# LNA_BFU550.net
KiCad netlist of a schematic drawn in Altium Designer
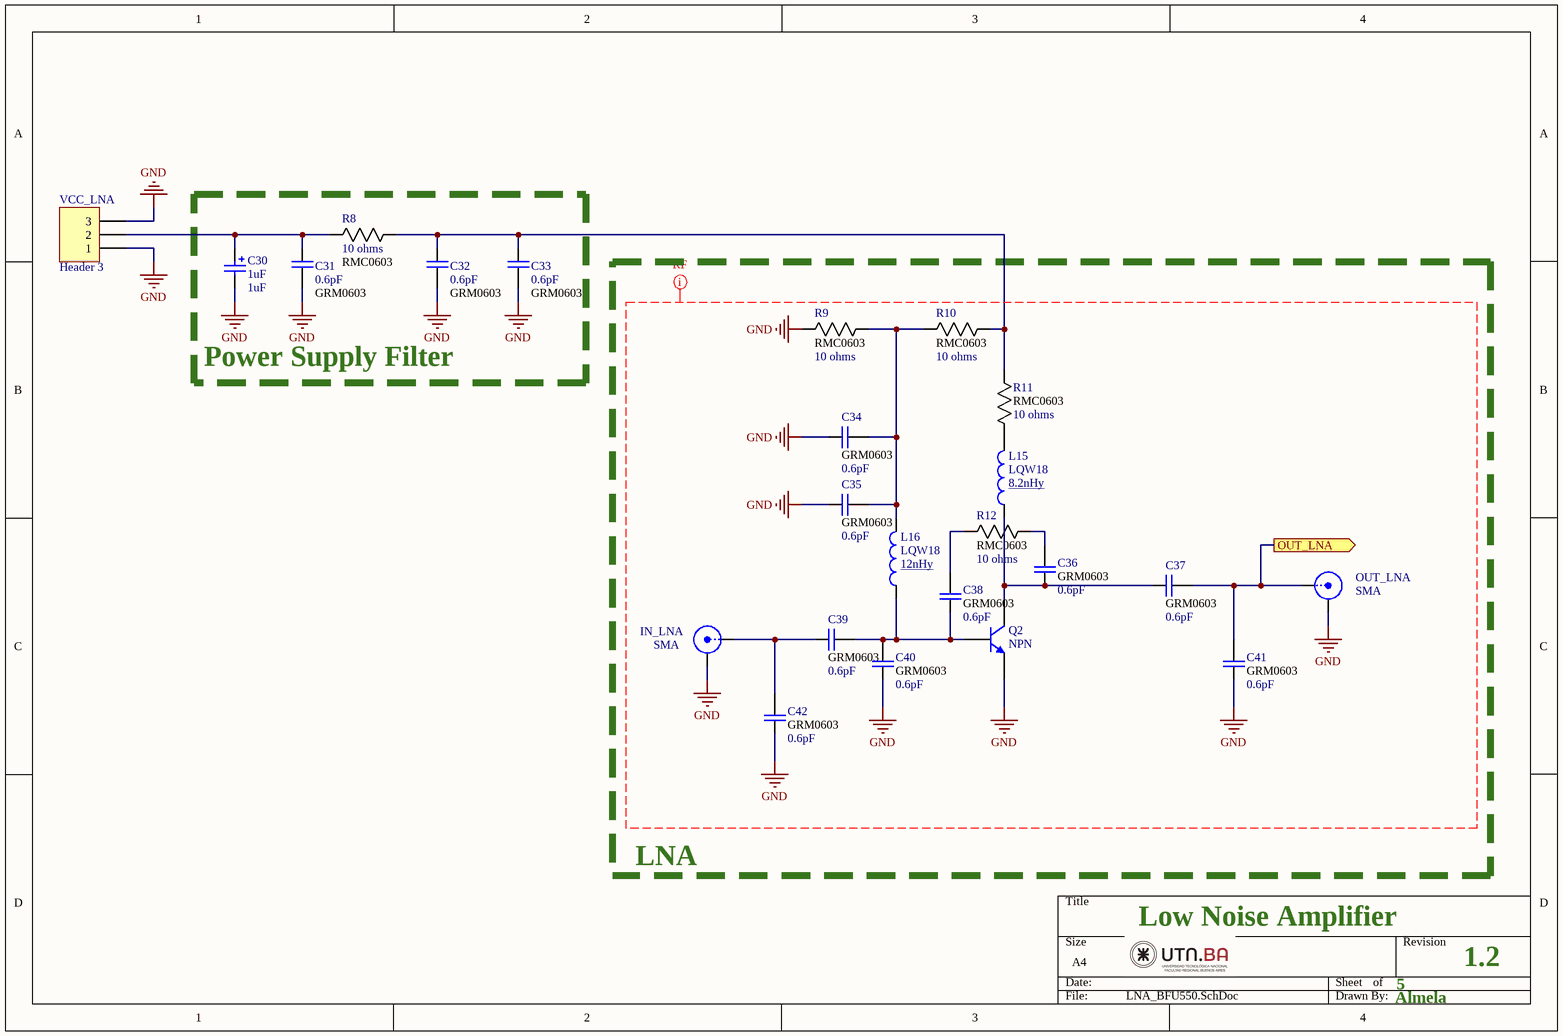
[diagram p0: LNA_BFU550.SchDoc]

(export (version "E")
  (design (tool "Eeschema 10.0.6"))
  (components
    (comp (ref "C30")
      (value "1uF")
      (footprint "6-0805_N")
      (description "Polarized Capacitor (Axial)")
      (fields (field (name "ALTIUM_VALUE") "1uF") (field (name "PUBLISHER") "Altium Limited"))
      (libsource (lib "PCB_Project") (part "Cap Pol2_1"))
    )
    (comp (ref "C31")
      (value "0.6pF")
      (footprint "GRM0603")
      (description "Capacitor GRM18 0603")
      (fields (field (name "Comment") "Cap 0603") (field (name "PUBLISHER") "Altium Limited"))
      (libsource (lib "Radar_RF_EAIII") (part "Cap"))
    )
    (comp (ref "C32")
      (value "0.6pF")
      (footprint "GRM0603")
      (description "Capacitor GRM18 0603")
      (fields (field (name "Comment") "Cap 0603") (field (name "PUBLISHER") "Altium Limited"))
      (libsource (lib "Radar_RF_EAIII") (part "Cap"))
    )
    (comp (ref "C33")
      (value "0.6pF")
      (footprint "GRM0603")
      (description "Capacitor GRM18 0603")
      (fields (field (name "Comment") "Cap 0603") (field (name "PUBLISHER") "Altium Limited"))
      (libsource (lib "Radar_RF_EAIII") (part "Cap"))
    )
    (comp (ref "C34")
      (value "0.6pF")
      (footprint "GRM0603")
      (description "Capacitor GRM18 0603")
      (fields (field (name "Comment") "Cap 0603") (field (name "PUBLISHER") "Altium Limited"))
      (libsource (lib "Radar_RF_EAIII") (part "Cap"))
    )
    (comp (ref "C35")
      (value "0.6pF")
      (footprint "GRM0603")
      (description "Capacitor GRM18 0603")
      (fields (field (name "Comment") "Cap 0603") (field (name "PUBLISHER") "Altium Limited"))
      (libsource (lib "Radar_RF_EAIII") (part "Cap"))
    )
    (comp (ref "C36")
      (value "0.6pF")
      (footprint "GRM0603")
      (description "Capacitor GRM18 0603")
      (fields (field (name "Comment") "Cap 0603") (field (name "PUBLISHER") "Altium Limited"))
      (libsource (lib "Radar_RF_EAIII") (part "Cap"))
    )
    (comp (ref "C37")
      (value "0.6pF")
      (footprint "GRM0603")
      (description "Capacitor GRM18 0603")
      (fields (field (name "Comment") "Cap 0603") (field (name "PUBLISHER") "Altium Limited"))
      (libsource (lib "Radar_RF_EAIII") (part "Cap"))
    )
    (comp (ref "C38")
      (value "0.6pF")
      (footprint "GRM0603")
      (description "Capacitor GRM18 0603")
      (fields (field (name "Comment") "Cap 0603") (field (name "PUBLISHER") "Altium Limited"))
      (libsource (lib "Radar_RF_EAIII") (part "Cap"))
    )
    (comp (ref "C39")
      (value "0.6pF")
      (footprint "GRM0603")
      (description "Capacitor GRM18 0603")
      (fields (field (name "Comment") "Cap 0603") (field (name "PUBLISHER") "Altium Limited"))
      (libsource (lib "Radar_RF_EAIII") (part "Cap"))
    )
    (comp (ref "C40")
      (value "0.6pF")
      (footprint "GRM0603")
      (description "Capacitor GRM18 0603")
      (fields (field (name "Comment") "Cap 0603") (field (name "PUBLISHER") "Altium Limited"))
      (libsource (lib "Radar_RF_EAIII") (part "Cap"))
    )
    (comp (ref "C41")
      (value "0.6pF")
      (footprint "GRM0603")
      (description "Capacitor GRM18 0603")
      (fields (field (name "Comment") "Cap 0603") (field (name "PUBLISHER") "Altium Limited"))
      (libsource (lib "Radar_RF_EAIII") (part "Cap"))
    )
    (comp (ref "C42")
      (value "0.6pF")
      (footprint "GRM0603")
      (description "Capacitor GRM18 0603")
      (fields (field (name "Comment") "Cap 0603") (field (name "PUBLISHER") "Altium Limited"))
      (libsource (lib "Radar_RF_EAIII") (part "Cap"))
    )
    (comp (ref "IN_LNA")
      (value "SMA")
      (footprint "SMA-142-0701-851")
      (description "SMB Straight Connector")
      (fields (field (name "PUBLISHER") "Altium Limited"))
      (libsource (lib "PCB_Project") (part "SMB"))
    )
    (comp (ref "L15")
      (value "LQW18")
      (footprint "INDC1608X100N")
      (description "Inductor LQW Package: 0603 (1608)")
      (fields
        (field (name "MP") "LQW18ANR47J00D")
        (field (name "MF") "Murata")
        (field (name "ALTIUM_VALUE") "8.2nHy")
      )
      (libsource (lib "Radar_RF_EAIII") (part "LQW18_1"))
    )
    (comp (ref "L16")
      (value "LQW18")
      (footprint "INDC1608X100N")
      (description "Inductor LQW Package: 0603 (1608)")
      (fields
        (field (name "MP") "LQW18ANR47J00D")
        (field (name "MF") "Murata")
        (field (name "ALTIUM_VALUE") "12nHy")
      )
      (libsource (lib "Radar_RF_EAIII") (part "LQW18_1"))
    )
    (comp (ref "OUT_LNA")
      (value "SMA")
      (footprint "SMA-142-0701-851")
      (description "SMB Straight Connector")
      (fields (field (name "PUBLISHER") "Altium Limited"))
      (libsource (lib "PCB_Project") (part "SMB"))
    )
    (comp (ref "Q2")
      (value "NPN")
      (footprint "SOT23_N_bfu550a")
      (description "NPN Bipolar Transistor")
      (fields (field (name "PUBLISHER") "Altium Limited"))
      (libsource (lib "Radar_RF_EAIII") (part "BFU550A"))
    )
    (comp (ref "R8")
      (value "10 ohms")
      (footprint "RMC0603")
      (description "Resistor RMC0603")
      (fields (field (name "Comment") "Resistor"))
      (libsource (lib "Radar_RF_EAIII") (part "Resistor"))
    )
    (comp (ref "R9")
      (value "10 ohms")
      (footprint "RMC0603")
      (description "Resistor RMC0603")
      (fields (field (name "Comment") "Resistor"))
      (libsource (lib "Radar_RF_EAIII") (part "Resistor"))
    )
    (comp (ref "R10")
      (value "10 ohms")
      (footprint "RMC0603")
      (description "Resistor RMC0603")
      (fields (field (name "Comment") "Resistor"))
      (libsource (lib "Radar_RF_EAIII") (part "Resistor"))
    )
    (comp (ref "R11")
      (value "10 ohms")
      (footprint "RMC0603")
      (description "Resistor RMC0603")
      (fields (field (name "Comment") "Resistor"))
      (libsource (lib "Radar_RF_EAIII") (part "Resistor"))
    )
    (comp (ref "R12")
      (value "10 ohms")
      (footprint "RMC0603")
      (description "Resistor RMC0603")
      (fields (field (name "Comment") "Resistor"))
      (libsource (lib "Radar_RF_EAIII") (part "Resistor"))
    )
    (comp (ref "VCC_LNA")
      (value "Header 3")
      (footprint "HDR1X3")
      (description "Header, 3-Pin")
      (fields (field (name "PUBLISHER") "Altium Limited"))
      (libsource (lib "Miscellaneous Connectors") (part "Header 3"))
    )
  )
  (nets
    (net (code "1") (name "/OUT_LNA") (class "Default")
      (node (ref "C37") (pin "2") (pinfunction "2_2") (pintype "passive"))
      (node (ref "C41") (pin "2") (pinfunction "2_2") (pintype "passive"))
      (node (ref "OUT_LNA") (pin "1") (pinfunction "X_1") (pintype "passive"))
    )
    (net (code "2") (name "GND") (class "Default")
      (node (ref "C30") (pin "2") (pinfunction "2_2") (pintype "passive"))
      (node (ref "C31") (pin "2") (pinfunction "2_2") (pintype "passive"))
      (node (ref "C32") (pin "2") (pinfunction "2_2") (pintype "passive"))
      (node (ref "C33") (pin "2") (pinfunction "2_2") (pintype "passive"))
      (node (ref "C34") (pin "1") (pinfunction "1_1") (pintype "passive"))
      (node (ref "C35") (pin "1") (pinfunction "1_1") (pintype "passive"))
      (node (ref "C40") (pin "1") (pinfunction "1_1") (pintype "passive"))
      (node (ref "C41") (pin "1") (pinfunction "1_1") (pintype "passive"))
      (node (ref "C42") (pin "1") (pinfunction "1_1") (pintype "passive"))
      (node (ref "IN_LNA") (pin "2") (pinfunction "Y_2") (pintype "passive"))
      (node (ref "OUT_LNA") (pin "2") (pinfunction "Y_2") (pintype "passive"))
      (node (ref "Q2") (pin "2") (pinfunction "E_2") (pintype "passive"))
      (node (ref "R9") (pin "2") (pinfunction "2_2") (pintype "passive"))
      (node (ref "VCC_LNA") (pin "1") (pinfunction "1_1") (pintype "passive"))
      (node (ref "VCC_LNA") (pin "3") (pinfunction "3_3") (pintype "passive"))
    )
    (net (code "3") (name "Net-(C30-Pad1)") (class "Default")
      (node (ref "C30") (pin "1") (pinfunction "1_1") (pintype "passive"))
      (node (ref "C31") (pin "1") (pinfunction "1_1") (pintype "passive"))
      (node (ref "R8") (pin "2") (pinfunction "2_2") (pintype "passive"))
      (node (ref "VCC_LNA") (pin "2") (pinfunction "2_2") (pintype "passive"))
    )
    (net (code "4") (name "Net-(C32-Pad1)") (class "Default")
      (node (ref "C32") (pin "1") (pinfunction "1_1") (pintype "passive"))
      (node (ref "C33") (pin "1") (pinfunction "1_1") (pintype "passive"))
      (node (ref "R10") (pin "2") (pinfunction "2_2") (pintype "passive"))
      (node (ref "R11") (pin "2") (pinfunction "2_2") (pintype "passive"))
      (node (ref "R8") (pin "1") (pinfunction "1_1") (pintype "passive"))
    )
    (net (code "5") (name "Net-(C34-Pad2)") (class "Default")
      (node (ref "C34") (pin "2") (pinfunction "2_2") (pintype "passive"))
      (node (ref "C35") (pin "2") (pinfunction "2_2") (pintype "passive"))
      (node (ref "L16") (pin "2") (pinfunction "2_2") (pintype "passive"))
      (node (ref "R10") (pin "1") (pinfunction "1_1") (pintype "passive"))
      (node (ref "R9") (pin "1") (pinfunction "1_1") (pintype "passive"))
    )
    (net (code "6") (name "Net-(C36-Pad2)") (class "Default")
      (node (ref "C36") (pin "2") (pinfunction "2_2") (pintype "passive"))
      (node (ref "R12") (pin "2") (pinfunction "2_2") (pintype "passive"))
    )
    (net (code "7") (name "Net-(C38-Pad2)") (class "Default")
      (node (ref "C38") (pin "2") (pinfunction "2_2") (pintype "passive"))
      (node (ref "R12") (pin "1") (pinfunction "1_1") (pintype "passive"))
    )
    (net (code "8") (name "Net-(IN_LNA-X)") (class "Default")
      (node (ref "C39") (pin "1") (pinfunction "1_1") (pintype "passive"))
      (node (ref "C42") (pin "2") (pinfunction "2_2") (pintype "passive"))
      (node (ref "IN_LNA") (pin "1") (pinfunction "X_1") (pintype "passive"))
    )
    (net (code "9") (name "Net-(L15-Pad2)") (class "Default")
      (node (ref "L15") (pin "2") (pinfunction "2_2") (pintype "passive"))
      (node (ref "R11") (pin "1") (pinfunction "1_1") (pintype "passive"))
    )
    (net (code "10") (name "Net-(Q2-B)") (class "Default")
      (node (ref "C38") (pin "1") (pinfunction "1_1") (pintype "passive"))
      (node (ref "C39") (pin "2") (pinfunction "2_2") (pintype "passive"))
      (node (ref "C40") (pin "2") (pinfunction "2_2") (pintype "passive"))
      (node (ref "L16") (pin "1") (pinfunction "1_1") (pintype "passive"))
      (node (ref "Q2") (pin "1") (pinfunction "B_1") (pintype "passive"))
    )
    (net (code "11") (name "Net-(Q2-C)") (class "Default")
      (node (ref "C36") (pin "1") (pinfunction "1_1") (pintype "passive"))
      (node (ref "C37") (pin "1") (pinfunction "1_1") (pintype "passive"))
      (node (ref "L15") (pin "1") (pinfunction "1_1") (pintype "passive"))
      (node (ref "Q2") (pin "3") (pinfunction "C_3") (pintype "passive"))
    )
  )
)
